# SensWear_SWD.net
KiCad netlist of a schematic drawn in Altium Designer
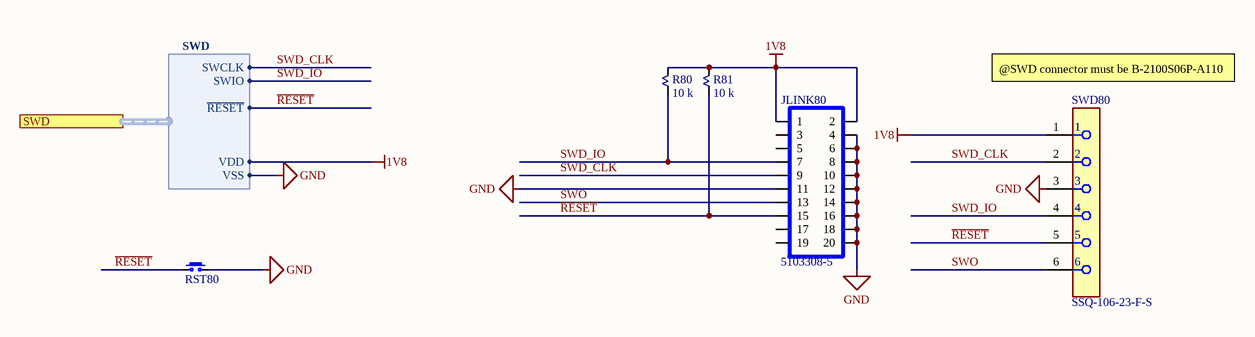
[diagram p0: SensWear_SWD.SchDoc]

(export (version "E")
  (design (tool "Eeschema 10.0.6"))
  (components
    (comp (ref "JLINK80")
      (value "5103308-5")
      (footprint "TE_5103308-5")
      (description "Header; Pin; Vertical; Copper Alloy; Thermoplastic; 20; 0.100 x 0.100 in.; 1 A")
      (fields (field (name "MANUFACTURER") "AMP - TE CONNECTIVITY"))
      (libsource (lib "SensWearComponents") (part "5103308-5"))
    )
    (comp (ref "R80")
      (value "10 k")
      (footprint "RESC1005X04N")
      (description "RES SMD 10K OHM 1% 1/10W 0402")
      (fields
        (field (name "MANUFACTURER") "Panasonic Electronic Components")
        (field (name "MANUFACTURER PART NUMBER") "ERJ-2RKF1002X")
      )
      (libsource (lib "SensWearComponents") (part "ERJ-2RKF1002X__2"))
    )
    (comp (ref "R81")
      (value "10 k")
      (footprint "RESC1005X04N")
      (description "RES SMD 10K OHM 1% 1/10W 0402")
      (fields
        (field (name "MANUFACTURER") "Panasonic Electronic Components")
        (field (name "MANUFACTURER PART NUMBER") "ERJ-2RKF1002X")
      )
      (libsource (lib "SensWearComponents") (part "ERJ-2RKF1002X__2"))
    )
    (comp (ref "RST80")
      (value "B3U-1000P")
      (footprint "B3U-1000P")
      (description "SWITCH TACTILE SPST-NO 0.05A 12V")
      (fields (field (name "MANUFACTURER") "Omron Electronics Inc-EMC Div"))
      (libsource (lib "SensWearComponents") (part "B3U-1000P"))
    )
    (comp (ref "SWD80")
      (value "SSQ-106-23-F-S")
      (footprint "FP-SSQ-106-23-F-S-MFG")
      (description "Headers & Wire Housings Tiger Buy Socket Strip with Square Tails, 0.100 Pitch")
      (fields (field (name "MANUFACTURER") "Samtec"))
      (libsource (lib "SensWearComponents") (part "SSQ-106-23-F-S"))
    )
  )
  (nets
    (net (code "2") (name "/SWD_CLK") (class "Default")
      (node (ref "JLINK80") (pin "9") (pinfunction "9_9") (pintype "passive"))
      (node (ref "SWD80") (pin "2") (pinfunction "2_2") (pintype "passive"))
    )
    (net (code "3") (name "/SWD_IO") (class "Default")
      (node (ref "JLINK80") (pin "7") (pinfunction "7_7") (pintype "passive"))
      (node (ref "R80") (pin "1") (pinfunction "1_1") (pintype "passive"))
      (node (ref "SWD80") (pin "4") (pinfunction "4_4") (pintype "passive"))
    )
    (net (code "4") (name "/SWO") (class "Default")
      (node (ref "JLINK80") (pin "13") (pinfunction "13_13") (pintype "passive"))
      (node (ref "SWD80") (pin "6") (pinfunction "6_6") (pintype "passive"))
    )
    (net (code "6") (name "/~{RESET}") (class "Default")
      (node (ref "JLINK80") (pin "15") (pinfunction "15_15") (pintype "passive"))
      (node (ref "R81") (pin "1") (pinfunction "1_1") (pintype "passive"))
      (node (ref "RST80") (pin "1") (pinfunction "1_1") (pintype "passive"))
      (node (ref "SWD80") (pin "5") (pinfunction "5_5") (pintype "passive"))
    )
    (net (code "7") (name "1V8") (class "Default")
      (node (ref "JLINK80") (pin "1") (pinfunction "1_1") (pintype "passive"))
      (node (ref "JLINK80") (pin "2") (pinfunction "2_2") (pintype "passive"))
      (node (ref "R80") (pin "2") (pinfunction "2_2") (pintype "passive"))
      (node (ref "R81") (pin "2") (pinfunction "2_2") (pintype "passive"))
      (node (ref "SWD80") (pin "1") (pinfunction "1_1") (pintype "passive"))
    )
    (net (code "8") (name "GND") (class "Default")
      (node (ref "JLINK80") (pin "10") (pinfunction "10_10") (pintype "passive"))
      (node (ref "JLINK80") (pin "11") (pinfunction "11_11") (pintype "passive"))
      (node (ref "JLINK80") (pin "12") (pinfunction "12_12") (pintype "passive"))
      (node (ref "JLINK80") (pin "14") (pinfunction "14_14") (pintype "passive"))
      (node (ref "JLINK80") (pin "16") (pinfunction "16_16") (pintype "passive"))
      (node (ref "JLINK80") (pin "18") (pinfunction "18_18") (pintype "passive"))
      (node (ref "JLINK80") (pin "20") (pinfunction "20_20") (pintype "passive"))
      (node (ref "JLINK80") (pin "4") (pinfunction "4_4") (pintype "passive"))
      (node (ref "JLINK80") (pin "6") (pinfunction "6_6") (pintype "passive"))
      (node (ref "JLINK80") (pin "8") (pinfunction "8_8") (pintype "passive"))
      (node (ref "RST80") (pin "2") (pinfunction "2_2") (pintype "passive"))
      (node (ref "SWD80") (pin "3") (pinfunction "3_3") (pintype "passive"))
    )
    (net (code "9") (name "unconnected-(JLINK80-Pad3)") (class "Default")
      (node (ref "JLINK80") (pin "3") (pinfunction "3_3") (pintype "passive"))
    )
    (net (code "10") (name "unconnected-(JLINK80-Pad5)") (class "Default")
      (node (ref "JLINK80") (pin "5") (pinfunction "5_5") (pintype "passive"))
    )
    (net (code "11") (name "unconnected-(JLINK80-Pad17)") (class "Default")
      (node (ref "JLINK80") (pin "17") (pinfunction "17_17") (pintype "passive"))
    )
    (net (code "12") (name "unconnected-(JLINK80-Pad19)") (class "Default")
      (node (ref "JLINK80") (pin "19") (pinfunction "19_19") (pintype "passive"))
    )
  )
)
